# SFPextensionSplit.net
KiCad netlist of a schematic drawn in Altium Designer
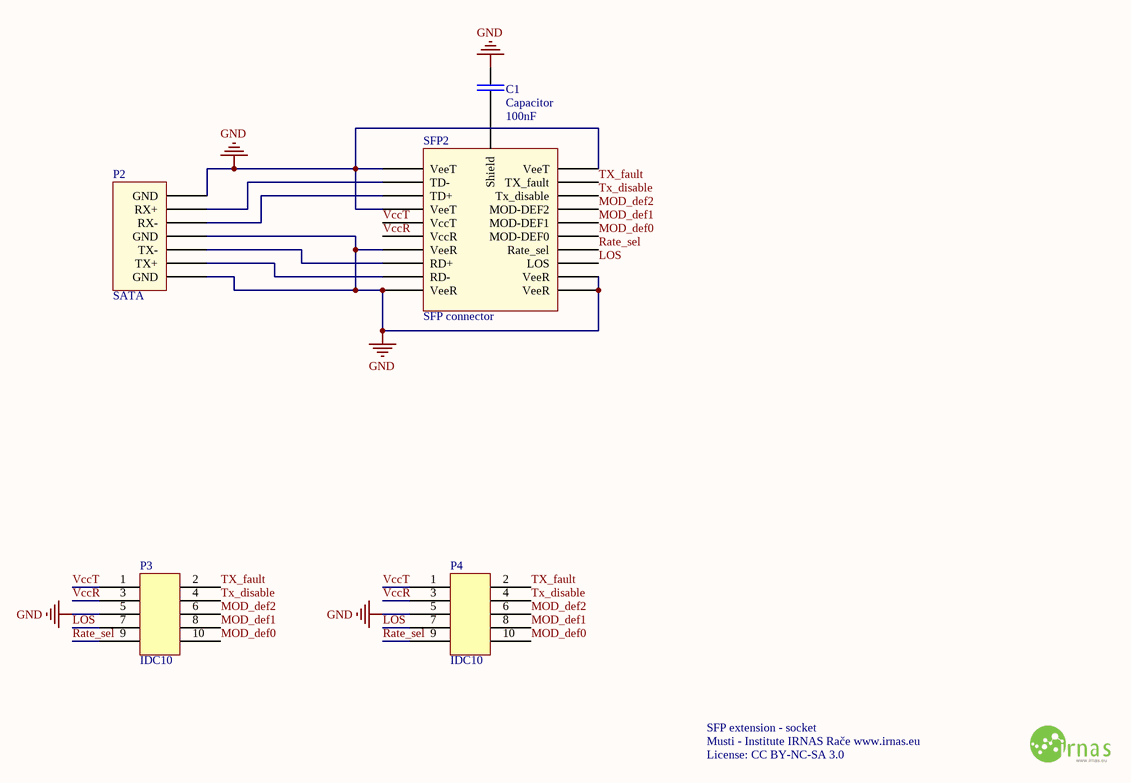
[diagram p0: SFPextensionSplit.SchDoc]

(export (version "E")
  (design (tool "Eeschema 10.0.6"))
  (components
    (comp (ref "C1")
      (value "Capacitor")
      (footprint "RESC2012X06N")
      (description "General capacitor")
      (fields (field (name "ALTIUM_VALUE") "100nF"))
      (libsource (lib "GeneralComponents") (part "Capacitor"))
    )
    (comp (ref "P2")
      (value "SATA")
      (footprint "SATA pcb")
      (description "sata")
      (libsource (lib "GeneralComponents") (part "SATA"))
    )
    (comp (ref "P3")
      (value "IDC10")
      (footprint "IDC10")
      (description "IDC 10pin")
      (libsource (lib "GeneralComponents") (part "IDC10"))
    )
    (comp (ref "P4")
      (value "IDC10")
      (footprint "IDC10")
      (description "IDC 10pin")
      (libsource (lib "GeneralComponents") (part "IDC10"))
    )
    (comp (ref "SFP2")
      (value "SFP connector")
      (footprint "SFP receptacle")
      (libsource (lib "GeneralComponents") (part "SFP connector"))
    )
  )
  (nets
    (net (code "1") (name "/LOS") (class "Default")
      (node (ref "P3") (pin "7") (pinfunction "7_7") (pintype "passive"))
      (node (ref "P4") (pin "7") (pinfunction "7_7") (pintype "passive"))
      (node (ref "SFP2") (pin "8") (pinfunction "LOS_8") (pintype "power_in"))
    )
    (net (code "2") (name "/MOD_def0") (class "Default")
      (node (ref "P3") (pin "10") (pinfunction "10_10") (pintype "passive"))
      (node (ref "P4") (pin "10") (pinfunction "10_10") (pintype "passive"))
      (node (ref "SFP2") (pin "6") (pinfunction "MOD-DEF0_6") (pintype "power_in"))
    )
    (net (code "3") (name "/MOD_def1") (class "Default")
      (node (ref "P3") (pin "8") (pinfunction "8_8") (pintype "passive"))
      (node (ref "P4") (pin "8") (pinfunction "8_8") (pintype "passive"))
      (node (ref "SFP2") (pin "5") (pinfunction "MOD-DEF1_5") (pintype "power_in"))
    )
    (net (code "4") (name "/MOD_def2") (class "Default")
      (node (ref "P3") (pin "6") (pinfunction "6_6") (pintype "passive"))
      (node (ref "P4") (pin "6") (pinfunction "6_6") (pintype "passive"))
      (node (ref "SFP2") (pin "4") (pinfunction "MOD-DEF2_4") (pintype "power_in"))
    )
    (net (code "5") (name "/Rate_sel") (class "Default")
      (node (ref "P3") (pin "9") (pinfunction "9_9") (pintype "passive"))
      (node (ref "P4") (pin "9") (pinfunction "9_9") (pintype "passive"))
      (node (ref "SFP2") (pin "7") (pinfunction "Rate_sel_7") (pintype "power_in"))
    )
    (net (code "6") (name "/TX_fault") (class "Default")
      (node (ref "P3") (pin "2") (pinfunction "2_2") (pintype "passive"))
      (node (ref "P4") (pin "2") (pinfunction "2_2") (pintype "passive"))
      (node (ref "SFP2") (pin "2") (pinfunction "TX_fault_2") (pintype "power_in"))
    )
    (net (code "7") (name "/Tx_disable") (class "Default")
      (node (ref "P3") (pin "4") (pinfunction "4_4") (pintype "passive"))
      (node (ref "P4") (pin "4") (pinfunction "4_4") (pintype "passive"))
      (node (ref "SFP2") (pin "3") (pinfunction "Tx_disable_3") (pintype "power_in"))
    )
    (net (code "8") (name "/VccR") (class "Default")
      (node (ref "P3") (pin "3") (pinfunction "3_3") (pintype "passive"))
      (node (ref "P4") (pin "3") (pinfunction "3_3") (pintype "passive"))
      (node (ref "SFP2") (pin "15") (pinfunction "VccR_15") (pintype "power_in"))
    )
    (net (code "9") (name "/VccT") (class "Default")
      (node (ref "P3") (pin "1") (pinfunction "A_1") (pintype "passive"))
      (node (ref "P4") (pin "1") (pinfunction "A_1") (pintype "passive"))
      (node (ref "SFP2") (pin "16") (pinfunction "VccT_16") (pintype "power_in"))
    )
    (net (code "10") (name "GND") (class "Default")
      (node (ref "C1") (pin "1") (pinfunction "1_1") (pintype "passive"))
      (node (ref "P2") (pin "1") (pinfunction "GND_1") (pintype "power_in"))
      (node (ref "P2") (pin "4") (pinfunction "GND_4") (pintype "power_in"))
      (node (ref "P2") (pin "7") (pinfunction "GND_7") (pintype "power_in"))
      (node (ref "P3") (pin "5") (pinfunction "5_5") (pintype "passive"))
      (node (ref "P4") (pin "5") (pinfunction "5_5") (pintype "passive"))
      (node (ref "SFP2") (pin "1") (pinfunction "VeeT_1") (pintype "power_in"))
      (node (ref "SFP2") (pin "10") (pinfunction "VeeR_10") (pintype "power_in"))
      (node (ref "SFP2") (pin "11") (pinfunction "VeeR_11") (pintype "power_in"))
      (node (ref "SFP2") (pin "14") (pinfunction "VeeR_14") (pintype "power_in"))
      (node (ref "SFP2") (pin "17") (pinfunction "VeeT_17") (pintype "power_in"))
      (node (ref "SFP2") (pin "20") (pinfunction "VeeT_20") (pintype "power_in"))
      (node (ref "SFP2") (pin "9") (pinfunction "VeeR_9") (pintype "power_in"))
    )
    (net (code "11") (name "Net-(P2-RX+)") (class "Default")
      (node (ref "P2") (pin "6") (pinfunction "RX+_6") (pintype "power_in"))
      (node (ref "SFP2") (pin "19") (pinfunction "TD-_19") (pintype "power_in"))
    )
    (net (code "12") (name "Net-(P2-RX-)") (class "Default")
      (node (ref "P2") (pin "5") (pinfunction "RX-_5") (pintype "power_in"))
      (node (ref "SFP2") (pin "18") (pinfunction "TD+_18") (pintype "power_in"))
    )
    (net (code "13") (name "Net-(P2-TX+)") (class "Default")
      (node (ref "P2") (pin "2") (pinfunction "TX+_2") (pintype "power_in"))
      (node (ref "SFP2") (pin "12") (pinfunction "RD-_12") (pintype "power_in"))
    )
    (net (code "14") (name "Net-(P2-TX-)") (class "Default")
      (node (ref "P2") (pin "3") (pinfunction "TX-_3") (pintype "power_in"))
      (node (ref "SFP2") (pin "13") (pinfunction "RD+_13") (pintype "power_in"))
    )
    (net (code "15") (name "Net-(SFP2-Shield)") (class "Default")
      (node (ref "C1") (pin "2") (pinfunction "2_2") (pintype "passive"))
      (node (ref "SFP2") (pin "21") (pinfunction "Shield_21") (pintype "power_in"))
    )
  )
)
